# ADC.net
KiCad netlist of a schematic drawn in Altium Designer
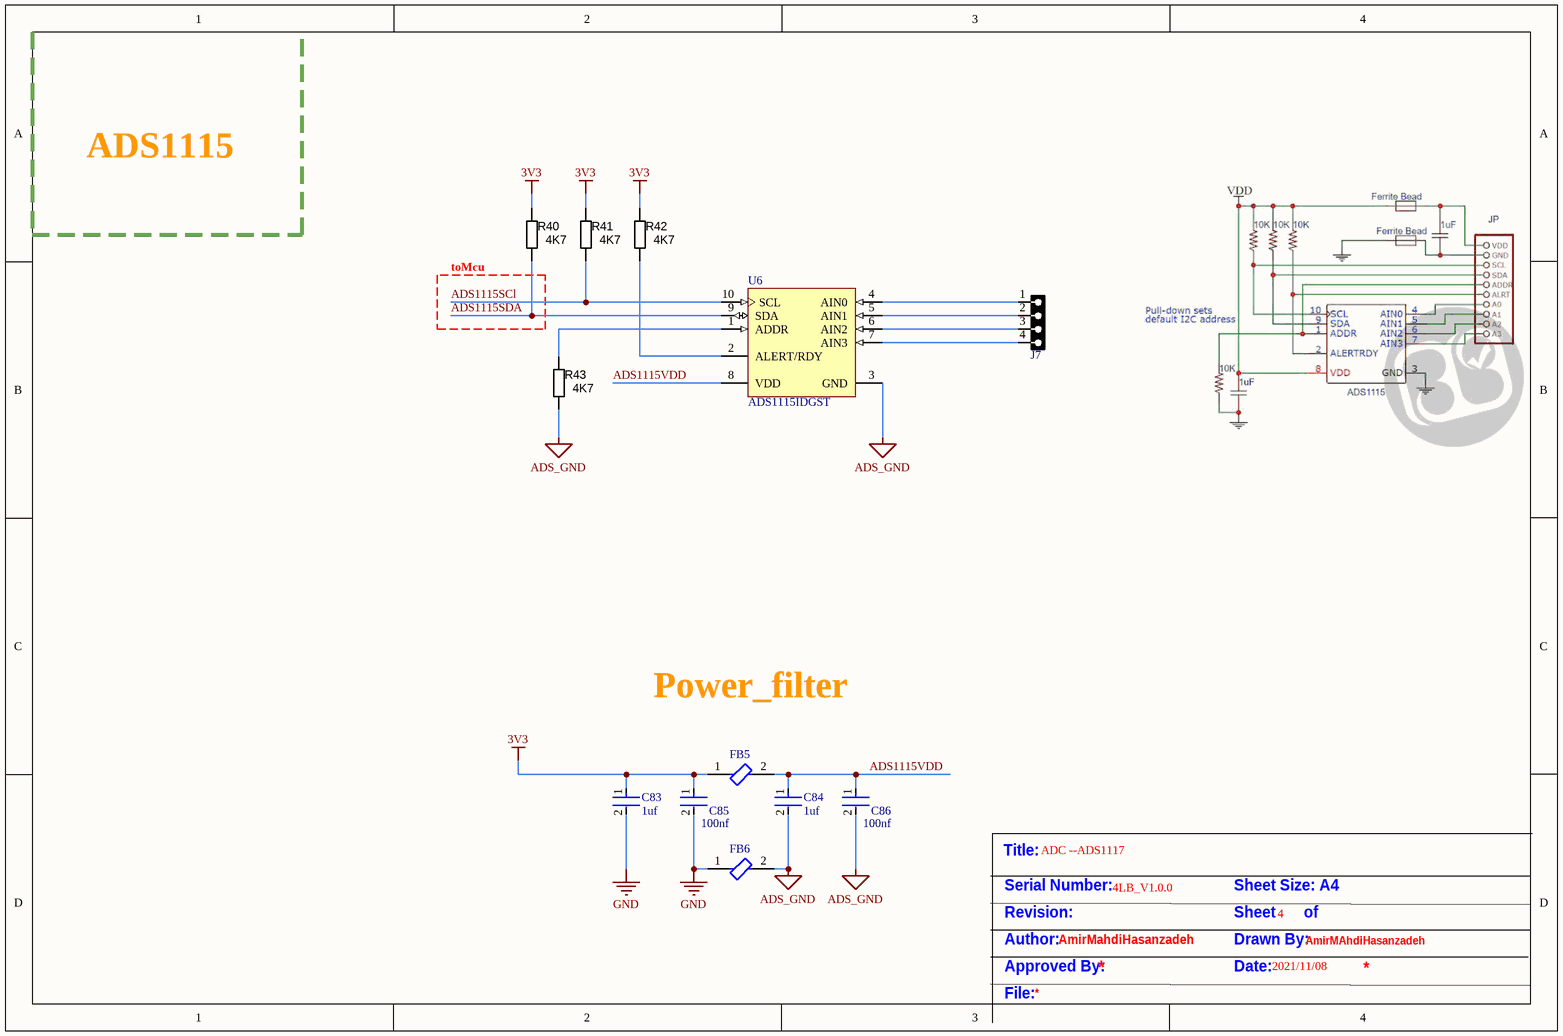
[diagram p0: ADC.SchDoc]

(export (version "E")
  (design (tool "Eeschema 10.0.6"))
  (components
    (comp (ref "C83")
      (value "1uf")
      (footprint "FP-GRM31C-0_2-e0_3_0_8-MFG")
      (description "Chip Multilayer Ceramic Capacitors for General Purpose, 1206, 10uF, X7R, 15%, 10%, 10V")
      (fields (field (name "VOLTAGE") "10V") (field (name "TOLERANCE") "10%"))
      (libsource (lib "Altium Content Vault") (part "02cd4be3c70576c341d710602a673aa"))
    )
    (comp (ref "C84")
      (value "1uf")
      (footprint "FP-GRM31C-0_2-e0_3_0_8-MFG")
      (description "Chip Multilayer Ceramic Capacitors for General Purpose, 1206, 10uF, X7R, 15%, 10%, 10V")
      (fields (field (name "VOLTAGE") "10V") (field (name "TOLERANCE") "10%"))
      (libsource (lib "Altium Content Vault") (part "02cd4be3c70576c341d710602a673aa"))
    )
    (comp (ref "C85")
      (value "100nf")
      (footprint "FP-CGA3E-0_3-0_1-IPC_A")
      (description "Cap Ceramic 100nF 50V X7R 10% Pad SMD 0603 +125°C Automotive T/R")
      (fields (field (name "TOLERANCE") "10%") (field (name "VOLTAGE") "50V"))
      (libsource (lib "Altium Content Vault") (part "b4654b650e69147ec39a6b967a45e02"))
    )
    (comp (ref "C86")
      (value "100nf")
      (footprint "FP-CGA3E-0_3-0_1-IPC_A")
      (description "Cap Ceramic 100nF 50V X7R 10% Pad SMD 0603 +125°C Automotive T/R")
      (fields (field (name "TOLERANCE") "10%") (field (name "VOLTAGE") "50V"))
      (libsource (lib "Altium Content Vault") (part "b4654b650e69147ec39a6b967a45e02"))
    )
    (comp (ref "FB5")
      (value "MMZ1608R600ATA00")
      (footprint "FP-MMZ1608-0_8-MFG")
      (description "Signal Line Ferrite Bead 60Ω  @ 100MHz 800mA DCR 100mΩ SMD 0603")
      (fields (field (name "TOLERANCE") "25%"))
      (libsource (lib "Altium Content Vault") (part "5f30dd21d616792df468990f7003faa"))
    )
    (comp (ref "FB6")
      (value "MMZ1608R600ATA00")
      (footprint "FP-MMZ1608-0_8-MFG")
      (description "Signal Line Ferrite Bead 60Ω  @ 100MHz 800mA DCR 100mΩ SMD 0603")
      (fields (field (name "TOLERANCE") "25%"))
      (libsource (lib "Altium Content Vault") (part "5f30dd21d616792df468990f7003faa"))
    )
    (comp (ref "J7")
      (value "HDRF4")
      (footprint "HDR_F_1X4")
      (description "CONN, HEADER, Female, pitch: 2.54mm, 4POS")
      (libsource (lib "conn_header_2.54_st") (part "HDR_F_1X4"))
    )
    (comp (ref "R40")
      (value "4K7")
      (footprint "RESC1608X55N")
      (description "Resistor SMD chip 4.7k Ohm 0.1W 5% 0603")
      (fields (field (name "TOLERANCE") "±5%") (field (name "Comment") "Thick Film"))
      (libsource (lib "PBL - Resistors") (part "RES_4K7_0603_5%"))
    )
    (comp (ref "R41")
      (value "4K7")
      (footprint "RESC1608X55N")
      (description "Resistor SMD chip 4.7k Ohm 0.1W 5% 0603")
      (fields (field (name "TOLERANCE") "±5%") (field (name "Comment") "Thick Film"))
      (libsource (lib "PBL - Resistors") (part "RES_4K7_0603_5%"))
    )
    (comp (ref "R42")
      (value "4K7")
      (footprint "RESC1608X55N")
      (description "Resistor SMD chip 4.7k Ohm 0.1W 5% 0603")
      (fields (field (name "TOLERANCE") "±5%") (field (name "Comment") "Thick Film"))
      (libsource (lib "PBL - Resistors") (part "RES_4K7_0603_5%"))
    )
    (comp (ref "R43")
      (value "4K7")
      (footprint "RESC1608X55N")
      (description "Resistor SMD chip 4.7k Ohm 0.1W 5% 0603")
      (fields (field (name "TOLERANCE") "±5%") (field (name "Comment") "Thick Film"))
      (libsource (lib "PBL - Resistors") (part "RES_4K7_0603_5%"))
    )
    (comp (ref "U6")
      (value "ADS1115IDGST")
      (footprint "TI-DGS10_M")
      (fields (field (name "MANUFACTURER") "Texas Instruments"))
      (libsource (lib "Altium Content Vault") (part "TI-ADS1015_1115-10"))
    )
  )
  (nets
    (net (code "1") (name "/ADS1115SCl") (class "Default")
      (node (ref "R41") (pin "2") (pinfunction "2_2") (pintype "passive"))
      (node (ref "U6") (pin "10") (pinfunction "SCL_10") (pintype "input"))
    )
    (net (code "2") (name "/ADS1115SDA") (class "Default")
      (node (ref "R40") (pin "2") (pinfunction "2_2") (pintype "passive"))
      (node (ref "U6") (pin "9") (pinfunction "SDA_9") (pintype "bidirectional"))
    )
    (net (code "3") (name "/ADS1115VDD") (class "Default")
      (node (ref "C84") (pin "1") (pinfunction "1_1") (pintype "passive"))
      (node (ref "C86") (pin "1") (pinfunction "1_1") (pintype "passive"))
      (node (ref "FB5") (pin "2") (pinfunction "2_2") (pintype "passive"))
      (node (ref "U6") (pin "8") (pinfunction "VDD_8") (pintype "power_in"))
    )
    (net (code "4") (name "3V3") (class "Default")
      (node (ref "C83") (pin "1") (pinfunction "1_1") (pintype "passive"))
      (node (ref "C85") (pin "1") (pinfunction "1_1") (pintype "passive"))
      (node (ref "FB5") (pin "1") (pinfunction "1_1") (pintype "passive"))
      (node (ref "R40") (pin "1") (pinfunction "1_1") (pintype "passive"))
      (node (ref "R41") (pin "1") (pinfunction "1_1") (pintype "passive"))
      (node (ref "R42") (pin "1") (pinfunction "1_1") (pintype "passive"))
    )
    (net (code "5") (name "ADS_GND") (class "Default")
      (node (ref "C84") (pin "2") (pinfunction "2_2") (pintype "passive"))
      (node (ref "C86") (pin "2") (pinfunction "2_2") (pintype "passive"))
      (node (ref "FB6") (pin "2") (pinfunction "2_2") (pintype "passive"))
      (node (ref "R43") (pin "2") (pinfunction "2_2") (pintype "passive"))
      (node (ref "U6") (pin "3") (pinfunction "GND_3") (pintype "power_in"))
    )
    (net (code "6") (name "GND") (class "Default")
      (node (ref "C83") (pin "2") (pinfunction "2_2") (pintype "passive"))
      (node (ref "C85") (pin "2") (pinfunction "2_2") (pintype "passive"))
      (node (ref "FB6") (pin "1") (pinfunction "1_1") (pintype "passive"))
    )
    (net (code "7") (name "Net-(U6-ADDR)") (class "Default")
      (node (ref "R43") (pin "1") (pinfunction "1_1") (pintype "passive"))
      (node (ref "U6") (pin "1") (pinfunction "ADDR_1") (pintype "input"))
    )
    (net (code "8") (name "Net-(U6-AIN0)") (class "Default")
      (node (ref "J7") (pin "1") (pinfunction "1_1") (pintype "passive"))
      (node (ref "U6") (pin "4") (pinfunction "AIN0_4") (pintype "input"))
    )
    (net (code "9") (name "Net-(U6-AIN1)") (class "Default")
      (node (ref "J7") (pin "2") (pinfunction "2_2") (pintype "passive"))
      (node (ref "U6") (pin "5") (pinfunction "AIN1_5") (pintype "input"))
    )
    (net (code "10") (name "Net-(U6-AIN2)") (class "Default")
      (node (ref "J7") (pin "3") (pinfunction "3_3") (pintype "passive"))
      (node (ref "U6") (pin "6") (pinfunction "AIN2_6") (pintype "input"))
    )
    (net (code "11") (name "Net-(U6-AIN3)") (class "Default")
      (node (ref "J7") (pin "4") (pinfunction "4_4") (pintype "passive"))
      (node (ref "U6") (pin "7") (pinfunction "AIN3_7") (pintype "input"))
    )
    (net (code "12") (name "Net-(U6-ALERT{slash}RDY)") (class "Default")
      (node (ref "R42") (pin "2") (pinfunction "2_2") (pintype "passive"))
      (node (ref "U6") (pin "2") (pinfunction "ALERT/RDY_2") (pintype "open_collector"))
    )
  )
)
